# version1.net
KiCad netlist of a schematic drawn in EAGLE
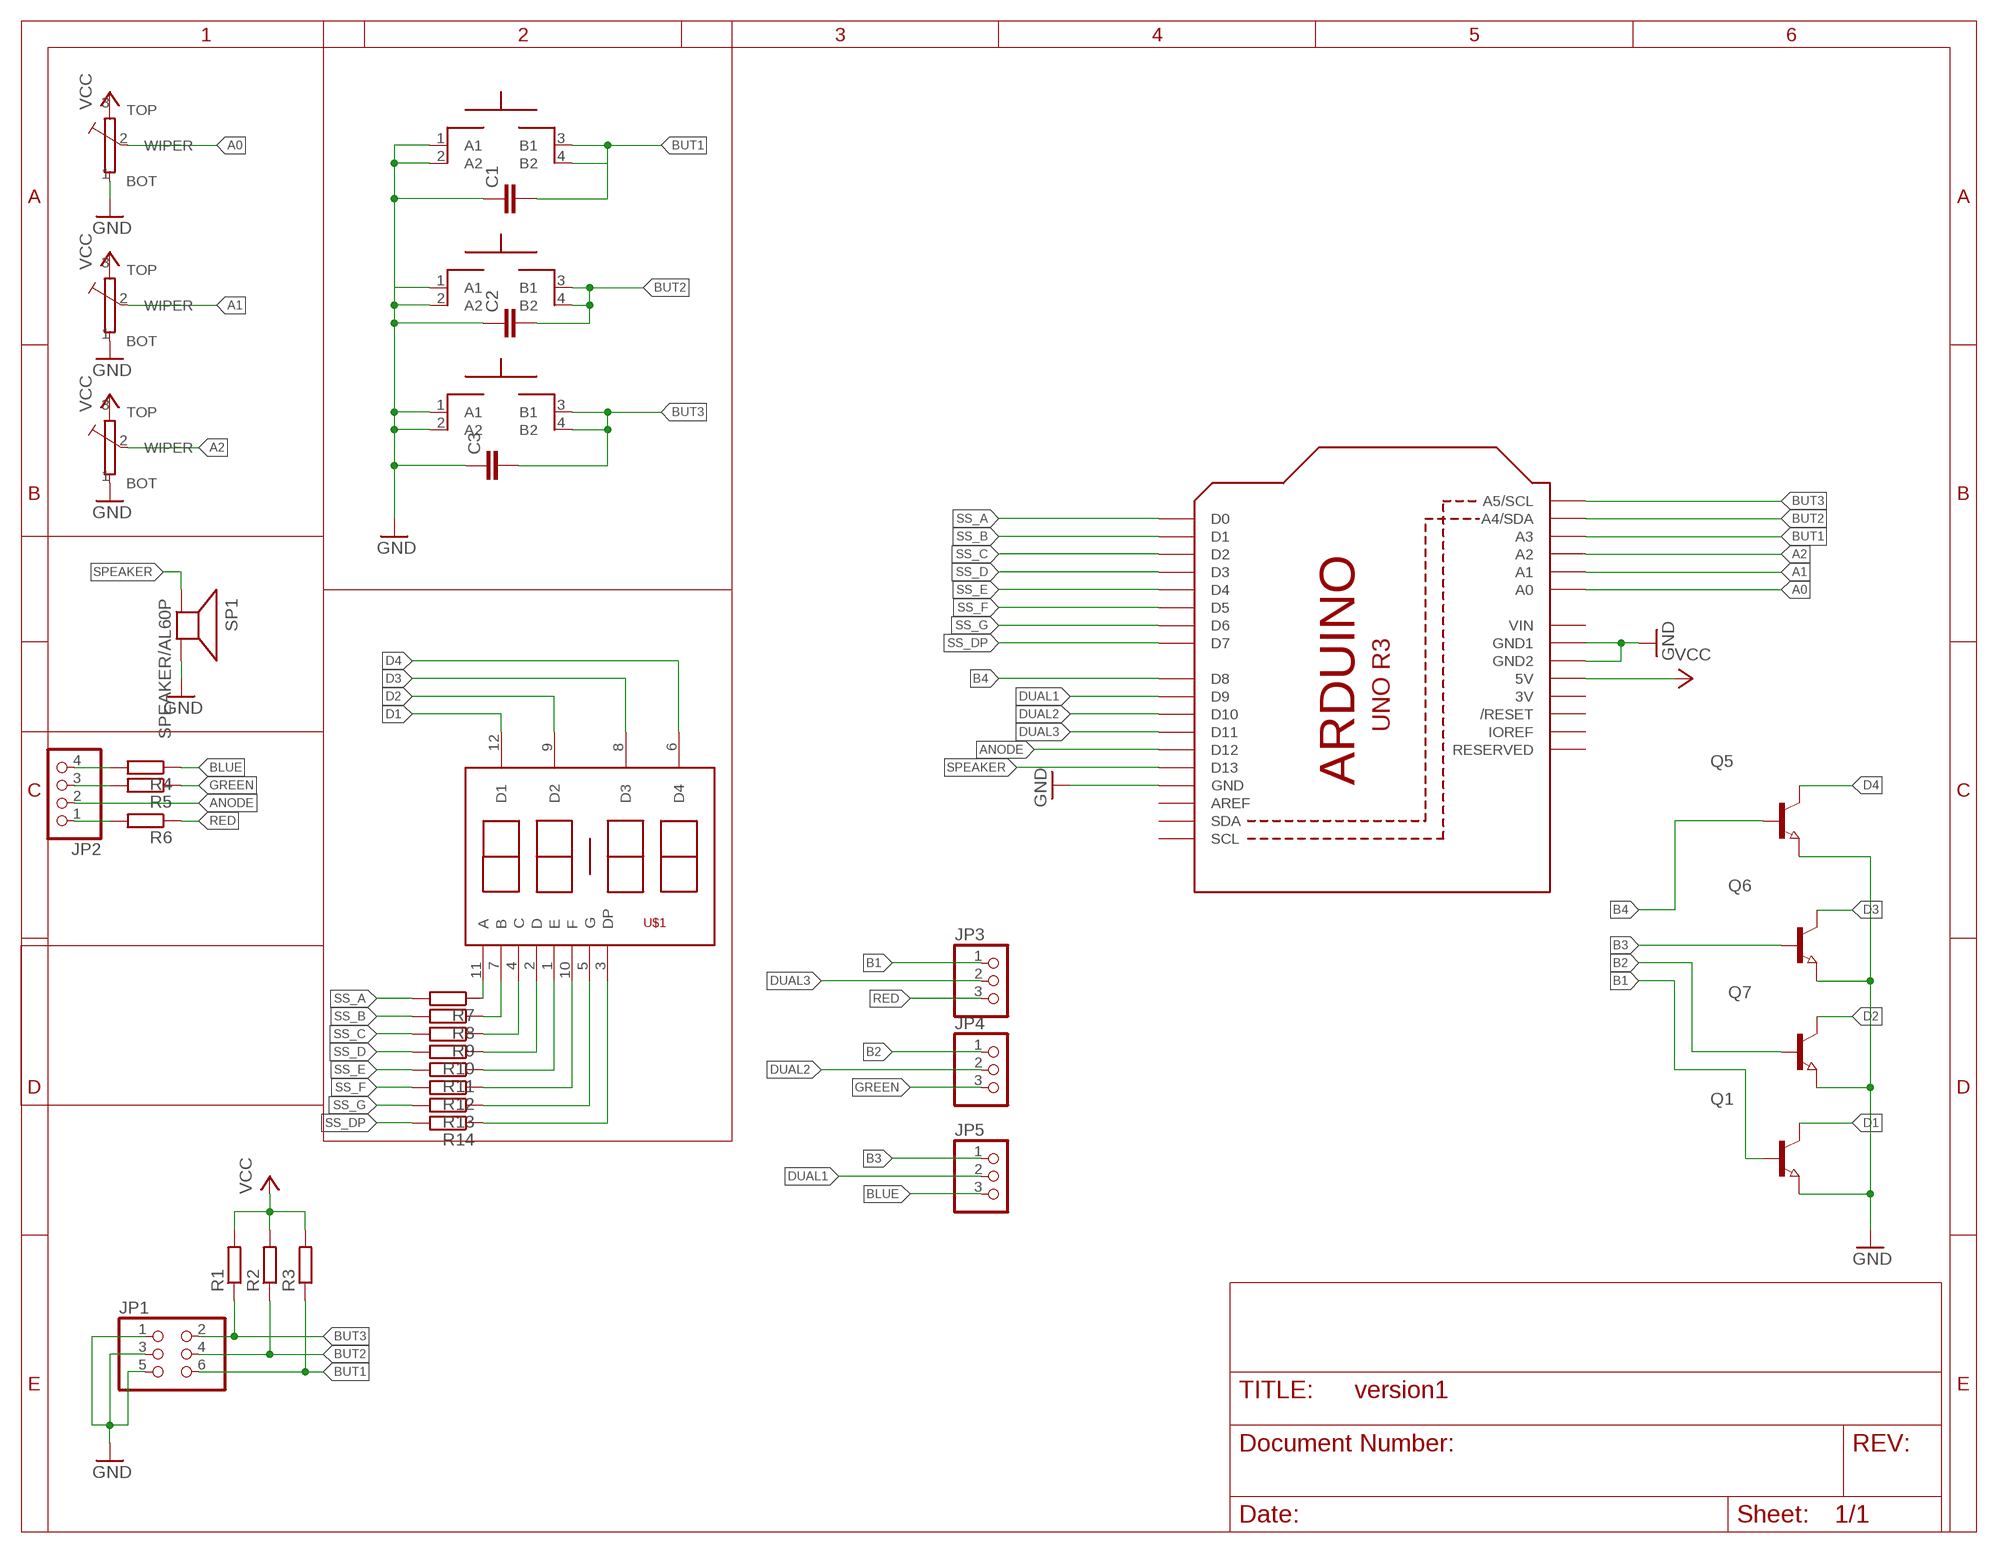
[diagram p0: schematic, sheet 1]

(export (version "E")
  (design (tool "Eeschema 10.0.6"))
  (components
    (comp (ref "C1")
      (value "C-EUC0805")
      (footprint "eagle-import:C0805")
      (libsource (lib "eagle-import") (part "C-EUC0805"))
    )
    (comp (ref "C2")
      (value "C-EUC0805")
      (footprint "eagle-import:C0805")
      (libsource (lib "eagle-import") (part "C-EUC0805"))
    )
    (comp (ref "C3")
      (value "C-EUC0805")
      (footprint "eagle-import:C0805")
      (libsource (lib "eagle-import") (part "C-EUC0805"))
    )
    (comp (ref "JP1")
      (value "PINHD-2X3")
      (footprint "eagle-import:2X03")
      (libsource (lib "eagle-import") (part "PINHD-2X3"))
    )
    (comp (ref "JP2")
      (value "PINHD-1X4")
      (footprint "eagle-import:1X04")
      (libsource (lib "eagle-import") (part "PINHD-1X4"))
    )
    (comp (ref "JP3")
      (value "PINHD-1X3")
      (footprint "eagle-import:1X03")
      (libsource (lib "eagle-import") (part "PINHD-1X3"))
    )
    (comp (ref "JP4")
      (value "PINHD-1X3")
      (footprint "eagle-import:1X03")
      (libsource (lib "eagle-import") (part "PINHD-1X3"))
    )
    (comp (ref "JP5")
      (value "PINHD-1X3")
      (footprint "eagle-import:1X03")
      (libsource (lib "eagle-import") (part "PINHD-1X3"))
    )
    (comp (ref "Q1")
      (value "NPN-TRANSISTOR_SOT23")
      (footprint "eagle-import:SOT23")
      (libsource (lib "eagle-import") (part "NPN-TRANSISTOR_SOT23"))
    )
    (comp (ref "Q5")
      (value "NPN-TRANSISTOR_SOT23")
      (footprint "eagle-import:SOT23")
      (libsource (lib "eagle-import") (part "NPN-TRANSISTOR_SOT23"))
    )
    (comp (ref "Q6")
      (value "NPN-TRANSISTOR_SOT23")
      (footprint "eagle-import:SOT23")
      (libsource (lib "eagle-import") (part "NPN-TRANSISTOR_SOT23"))
    )
    (comp (ref "Q7")
      (value "NPN-TRANSISTOR_SOT23")
      (footprint "eagle-import:SOT23")
      (libsource (lib "eagle-import") (part "NPN-TRANSISTOR_SOT23"))
    )
    (comp (ref "R1")
      (value "R-EU_R0805")
      (footprint "eagle-import:R0805")
      (libsource (lib "eagle-import") (part "R-EU_R0805"))
    )
    (comp (ref "R2")
      (value "R-EU_R0805")
      (footprint "eagle-import:R0805")
      (libsource (lib "eagle-import") (part "R-EU_R0805"))
    )
    (comp (ref "R3")
      (value "R-EU_R0805")
      (footprint "eagle-import:R0805")
      (libsource (lib "eagle-import") (part "R-EU_R0805"))
    )
    (comp (ref "R4")
      (value "R-EU_R0805")
      (footprint "eagle-import:R0805")
      (libsource (lib "eagle-import") (part "R-EU_R0805"))
    )
    (comp (ref "R5")
      (value "R-EU_R0805")
      (footprint "eagle-import:R0805")
      (libsource (lib "eagle-import") (part "R-EU_R0805"))
    )
    (comp (ref "R6")
      (value "R-EU_R0805")
      (footprint "eagle-import:R0805")
      (libsource (lib "eagle-import") (part "R-EU_R0805"))
    )
    (comp (ref "R7")
      (value "R-EU_R0805")
      (footprint "eagle-import:R0805")
      (libsource (lib "eagle-import") (part "R-EU_R0805"))
    )
    (comp (ref "R8")
      (value "R-EU_R0805")
      (footprint "eagle-import:R0805")
      (libsource (lib "eagle-import") (part "R-EU_R0805"))
    )
    (comp (ref "R9")
      (value "R-EU_R0805")
      (footprint "eagle-import:R0805")
      (libsource (lib "eagle-import") (part "R-EU_R0805"))
    )
    (comp (ref "R10")
      (value "R-EU_R0805")
      (footprint "eagle-import:R0805")
      (libsource (lib "eagle-import") (part "R-EU_R0805"))
    )
    (comp (ref "R11")
      (value "R-EU_R0805")
      (footprint "eagle-import:R0805")
      (libsource (lib "eagle-import") (part "R-EU_R0805"))
    )
    (comp (ref "R12")
      (value "R-EU_R0805")
      (footprint "eagle-import:R0805")
      (libsource (lib "eagle-import") (part "R-EU_R0805"))
    )
    (comp (ref "R13")
      (value "R-EU_R0805")
      (footprint "eagle-import:R0805")
      (libsource (lib "eagle-import") (part "R-EU_R0805"))
    )
    (comp (ref "R14")
      (value "R-EU_R0805")
      (footprint "eagle-import:R0805")
      (libsource (lib "eagle-import") (part "R-EU_R0805"))
    )
    (comp (ref "SP1")
      (value "SPEAKER/AL60P")
      (footprint "eagle-import:AL60P")
      (libsource (lib "eagle-import") (part "SPEAKER/AL60P"))
    )
    (comp (ref "SW1")
      (value "MOMENTARYBUTTON")
      (footprint "eagle-import:SPST_NO_SMD")
      (libsource (lib "eagle-import") (part "MOMENTARYBUTTON"))
    )
    (comp (ref "SW2")
      (value "MOMENTARYBUTTON")
      (footprint "eagle-import:SPST_NO_SMD")
      (libsource (lib "eagle-import") (part "MOMENTARYBUTTON"))
    )
    (comp (ref "SW3")
      (value "MOMENTARYBUTTON")
      (footprint "eagle-import:SPST_NO_SMD")
      (libsource (lib "eagle-import") (part "MOMENTARYBUTTON"))
    )
    (comp (ref "TR1")
      (value "TRIMMTHUMB")
      (footprint "eagle-import:RV09")
      (libsource (lib "eagle-import") (part "TRIMMTHUMB"))
    )
    (comp (ref "TR2")
      (value "TRIMMTHUMB")
      (footprint "eagle-import:RV09")
      (libsource (lib "eagle-import") (part "TRIMMTHUMB"))
    )
    (comp (ref "TR3")
      (value "TRIMMTHUMB")
      (footprint "eagle-import:RV09")
      (libsource (lib "eagle-import") (part "TRIMMTHUMB"))
    )
    (comp (ref "U$1")
      (value "4DIG_7SEG_CATHODE")
      (footprint "eagle-import:4DIG_7SEG_CLOCK")
      (libsource (lib "eagle-import") (part "4DIG_7SEG_CATHODE"))
    )
    (comp (ref "U1")
      (value "ARDUINOR3-BPLACE")
      (footprint "eagle-import:ARDUINOR3-BPLACE")
      (libsource (lib "eagle-import") (part "ARDUINOR3-BPLACE"))
    )
  )
  (nets
    (net (code "1") (name "/3V") (class "Default")
      (node (ref "U1") (pin "3V") (pinfunction "3V_3V") (pintype "power_in"))
    )
    (net (code "2") (name "/VIN") (class "Default")
      (node (ref "U1") (pin "VIN") (pinfunction "VIN_VIN") (pintype "power_in"))
    )
    (net (code "3") (name "A0") (class "Default")
      (node (ref "TR1") (pin "2") (pinfunction "WIPER_2") (pintype "bidirectional"))
      (node (ref "U1") (pin "A0") (pinfunction "A0_A0") (pintype "bidirectional"))
    )
    (net (code "4") (name "A1") (class "Default")
      (node (ref "TR2") (pin "2") (pinfunction "WIPER_2") (pintype "bidirectional"))
      (node (ref "U1") (pin "A1") (pinfunction "A1_A1") (pintype "bidirectional"))
    )
    (net (code "5") (name "A2") (class "Default")
      (node (ref "TR3") (pin "2") (pinfunction "WIPER_2") (pintype "bidirectional"))
      (node (ref "U1") (pin "A2") (pinfunction "A2_A2") (pintype "bidirectional"))
    )
    (net (code "6") (name "ANODE") (class "Default")
      (node (ref "JP2") (pin "2") (pinfunction "2_2") (pintype "passive"))
      (node (ref "U1") (pin "D12") (pinfunction "D12_D12") (pintype "bidirectional"))
    )
    (net (code "7") (name "B1") (class "Default")
      (node (ref "JP3") (pin "1") (pinfunction "1_1") (pintype "passive"))
      (node (ref "Q1") (pin "1") (pinfunction "B_1") (pintype "passive"))
    )
    (net (code "8") (name "B2") (class "Default")
      (node (ref "JP4") (pin "1") (pinfunction "1_1") (pintype "passive"))
      (node (ref "Q7") (pin "1") (pinfunction "B_1") (pintype "passive"))
    )
    (net (code "9") (name "B3") (class "Default")
      (node (ref "JP5") (pin "1") (pinfunction "1_1") (pintype "passive"))
      (node (ref "Q6") (pin "1") (pinfunction "B_1") (pintype "passive"))
    )
    (net (code "10") (name "B4") (class "Default")
      (node (ref "Q5") (pin "1") (pinfunction "B_1") (pintype "passive"))
      (node (ref "U1") (pin "D8") (pinfunction "D8_D8") (pintype "bidirectional"))
    )
    (net (code "11") (name "BLUE") (class "Default")
      (node (ref "JP5") (pin "3") (pinfunction "3_3") (pintype "passive"))
      (node (ref "R4") (pin "1") (pinfunction "1_1") (pintype "passive"))
    )
    (net (code "12") (name "BUT1") (class "Default")
      (node (ref "C1") (pin "2") (pinfunction "2_2") (pintype "passive"))
      (node (ref "JP1") (pin "6") (pinfunction "6_6") (pintype "passive"))
      (node (ref "R3") (pin "1") (pinfunction "1_1") (pintype "passive"))
      (node (ref "SW1") (pin "3") (pinfunction "B1_3") (pintype "bidirectional"))
      (node (ref "SW1") (pin "4") (pinfunction "B2_4") (pintype "bidirectional"))
      (node (ref "U1") (pin "A3") (pinfunction "A3_A3") (pintype "bidirectional"))
    )
    (net (code "13") (name "BUT2") (class "Default")
      (node (ref "C2") (pin "2") (pinfunction "2_2") (pintype "passive"))
      (node (ref "JP1") (pin "4") (pinfunction "4_4") (pintype "passive"))
      (node (ref "R2") (pin "1") (pinfunction "1_1") (pintype "passive"))
      (node (ref "SW2") (pin "3") (pinfunction "B1_3") (pintype "bidirectional"))
      (node (ref "SW2") (pin "4") (pinfunction "B2_4") (pintype "bidirectional"))
      (node (ref "U1") (pin "A4") (pinfunction "A4/SDA_A4") (pintype "bidirectional"))
    )
    (net (code "14") (name "BUT3") (class "Default")
      (node (ref "C3") (pin "2") (pinfunction "2_2") (pintype "passive"))
      (node (ref "JP1") (pin "2") (pinfunction "2_2") (pintype "passive"))
      (node (ref "R1") (pin "1") (pinfunction "1_1") (pintype "passive"))
      (node (ref "SW3") (pin "3") (pinfunction "B1_3") (pintype "bidirectional"))
      (node (ref "SW3") (pin "4") (pinfunction "B2_4") (pintype "bidirectional"))
      (node (ref "U1") (pin "A5") (pinfunction "A5/SCL_A5") (pintype "bidirectional"))
    )
    (net (code "15") (name "D1") (class "Default")
      (node (ref "Q1") (pin "3") (pinfunction "C_3") (pintype "passive"))
      (node (ref "U$1") (pin "12") (pinfunction "D1_12") (pintype "bidirectional"))
    )
    (net (code "16") (name "D2") (class "Default")
      (node (ref "Q7") (pin "3") (pinfunction "C_3") (pintype "passive"))
      (node (ref "U$1") (pin "9") (pinfunction "D2_9") (pintype "bidirectional"))
    )
    (net (code "17") (name "D3") (class "Default")
      (node (ref "Q6") (pin "3") (pinfunction "C_3") (pintype "passive"))
      (node (ref "U$1") (pin "8") (pinfunction "D3_8") (pintype "bidirectional"))
    )
    (net (code "18") (name "D4") (class "Default")
      (node (ref "Q5") (pin "3") (pinfunction "C_3") (pintype "passive"))
      (node (ref "U$1") (pin "6") (pinfunction "D4_6") (pintype "bidirectional"))
    )
    (net (code "19") (name "DUAL1") (class "Default")
      (node (ref "JP5") (pin "2") (pinfunction "2_2") (pintype "passive"))
      (node (ref "U1") (pin "D9") (pinfunction "D9_D9") (pintype "bidirectional"))
    )
    (net (code "20") (name "DUAL2") (class "Default")
      (node (ref "JP4") (pin "2") (pinfunction "2_2") (pintype "passive"))
      (node (ref "U1") (pin "D10") (pinfunction "D10_D10") (pintype "bidirectional"))
    )
    (net (code "21") (name "DUAL3") (class "Default")
      (node (ref "JP3") (pin "2") (pinfunction "2_2") (pintype "passive"))
      (node (ref "U1") (pin "D11") (pinfunction "D11_D11") (pintype "bidirectional"))
    )
    (net (code "22") (name "GND") (class "Default")
      (node (ref "C1") (pin "1") (pinfunction "1_1") (pintype "passive"))
      (node (ref "C2") (pin "1") (pinfunction "1_1") (pintype "passive"))
      (node (ref "C3") (pin "1") (pinfunction "1_1") (pintype "passive"))
      (node (ref "JP1") (pin "1") (pinfunction "1_1") (pintype "passive"))
      (node (ref "JP1") (pin "3") (pinfunction "3_3") (pintype "passive"))
      (node (ref "JP1") (pin "5") (pinfunction "5_5") (pintype "passive"))
      (node (ref "Q1") (pin "2") (pinfunction "E_2") (pintype "passive"))
      (node (ref "Q5") (pin "2") (pinfunction "E_2") (pintype "passive"))
      (node (ref "Q6") (pin "2") (pinfunction "E_2") (pintype "passive"))
      (node (ref "Q7") (pin "2") (pinfunction "E_2") (pintype "passive"))
      (node (ref "SP1") (pin "2") (pinfunction "-_2") (pintype "passive"))
      (node (ref "SW1") (pin "1") (pinfunction "A1_1") (pintype "bidirectional"))
      (node (ref "SW1") (pin "2") (pinfunction "A2_2") (pintype "bidirectional"))
      (node (ref "SW2") (pin "1") (pinfunction "A1_1") (pintype "bidirectional"))
      (node (ref "SW2") (pin "2") (pinfunction "A2_2") (pintype "bidirectional"))
      (node (ref "SW3") (pin "1") (pinfunction "A1_1") (pintype "bidirectional"))
      (node (ref "SW3") (pin "2") (pinfunction "A2_2") (pintype "bidirectional"))
      (node (ref "TR1") (pin "1") (pinfunction "BOT_1") (pintype "bidirectional"))
      (node (ref "TR2") (pin "1") (pinfunction "BOT_1") (pintype "bidirectional"))
      (node (ref "TR3") (pin "1") (pinfunction "BOT_1") (pintype "bidirectional"))
      (node (ref "U1") (pin "GND") (pinfunction "GND_GND") (pintype "power_in"))
      (node (ref "U1") (pin "GND1") (pinfunction "GND1_GND1") (pintype "power_in"))
      (node (ref "U1") (pin "GND2") (pinfunction "GND2_GND2") (pintype "power_in"))
    )
    (net (code "23") (name "GREEN") (class "Default")
      (node (ref "JP4") (pin "3") (pinfunction "3_3") (pintype "passive"))
      (node (ref "R5") (pin "1") (pinfunction "1_1") (pintype "passive"))
    )
    (net (code "24") (name "Net-(JP2-Pad1)") (class "Default")
      (node (ref "JP2") (pin "1") (pinfunction "1_1") (pintype "passive"))
      (node (ref "R6") (pin "2") (pinfunction "2_2") (pintype "passive"))
    )
    (net (code "25") (name "Net-(JP2-Pad3)") (class "Default")
      (node (ref "JP2") (pin "3") (pinfunction "3_3") (pintype "passive"))
      (node (ref "R5") (pin "2") (pinfunction "2_2") (pintype "passive"))
    )
    (net (code "26") (name "Net-(JP2-Pad4)") (class "Default")
      (node (ref "JP2") (pin "4") (pinfunction "4_4") (pintype "passive"))
      (node (ref "R4") (pin "2") (pinfunction "2_2") (pintype "passive"))
    )
    (net (code "27") (name "Net-(U$1-A)") (class "Default")
      (node (ref "R7") (pin "1") (pinfunction "1_1") (pintype "passive"))
      (node (ref "U$1") (pin "11") (pinfunction "A_11") (pintype "bidirectional"))
    )
    (net (code "28") (name "Net-(U$1-B)") (class "Default")
      (node (ref "R8") (pin "1") (pinfunction "1_1") (pintype "passive"))
      (node (ref "U$1") (pin "7") (pinfunction "B_7") (pintype "bidirectional"))
    )
    (net (code "29") (name "Net-(U$1-C)") (class "Default")
      (node (ref "R9") (pin "1") (pinfunction "1_1") (pintype "passive"))
      (node (ref "U$1") (pin "4") (pinfunction "C_4") (pintype "bidirectional"))
    )
    (net (code "30") (name "Net-(U$1-D)") (class "Default")
      (node (ref "R10") (pin "1") (pinfunction "1_1") (pintype "passive"))
      (node (ref "U$1") (pin "2") (pinfunction "D_2") (pintype "bidirectional"))
    )
    (net (code "31") (name "Net-(U$1-DP)") (class "Default")
      (node (ref "R14") (pin "1") (pinfunction "1_1") (pintype "passive"))
      (node (ref "U$1") (pin "3") (pinfunction "DP_3") (pintype "bidirectional"))
    )
    (net (code "32") (name "Net-(U$1-E)") (class "Default")
      (node (ref "R11") (pin "1") (pinfunction "1_1") (pintype "passive"))
      (node (ref "U$1") (pin "1") (pinfunction "E_1") (pintype "bidirectional"))
    )
    (net (code "33") (name "Net-(U$1-F)") (class "Default")
      (node (ref "R12") (pin "1") (pinfunction "1_1") (pintype "passive"))
      (node (ref "U$1") (pin "10") (pinfunction "F_10") (pintype "bidirectional"))
    )
    (net (code "34") (name "Net-(U$1-G)") (class "Default")
      (node (ref "R13") (pin "1") (pinfunction "1_1") (pintype "passive"))
      (node (ref "U$1") (pin "5") (pinfunction "G_5") (pintype "bidirectional"))
    )
    (net (code "35") (name "RED") (class "Default")
      (node (ref "JP3") (pin "3") (pinfunction "3_3") (pintype "passive"))
      (node (ref "R6") (pin "1") (pinfunction "1_1") (pintype "passive"))
    )
    (net (code "36") (name "SPEAKER") (class "Default")
      (node (ref "SP1") (pin "1") (pinfunction "+_1") (pintype "passive"))
      (node (ref "U1") (pin "D13") (pinfunction "D13_D13") (pintype "bidirectional"))
    )
    (net (code "37") (name "SS_A") (class "Default")
      (node (ref "R7") (pin "2") (pinfunction "2_2") (pintype "passive"))
      (node (ref "U1") (pin "D0") (pinfunction "D0_D0") (pintype "bidirectional"))
    )
    (net (code "38") (name "SS_B") (class "Default")
      (node (ref "R8") (pin "2") (pinfunction "2_2") (pintype "passive"))
      (node (ref "U1") (pin "D1") (pinfunction "D1_D1") (pintype "bidirectional"))
    )
    (net (code "39") (name "SS_C") (class "Default")
      (node (ref "R9") (pin "2") (pinfunction "2_2") (pintype "passive"))
      (node (ref "U1") (pin "D2") (pinfunction "D2_D2") (pintype "bidirectional"))
    )
    (net (code "40") (name "SS_D") (class "Default")
      (node (ref "R10") (pin "2") (pinfunction "2_2") (pintype "passive"))
      (node (ref "U1") (pin "D3") (pinfunction "D3_D3") (pintype "bidirectional"))
    )
    (net (code "41") (name "SS_DP") (class "Default")
      (node (ref "R14") (pin "2") (pinfunction "2_2") (pintype "passive"))
      (node (ref "U1") (pin "D7") (pinfunction "D7_D7") (pintype "bidirectional"))
    )
    (net (code "42") (name "SS_E") (class "Default")
      (node (ref "R11") (pin "2") (pinfunction "2_2") (pintype "passive"))
      (node (ref "U1") (pin "D4") (pinfunction "D4_D4") (pintype "bidirectional"))
    )
    (net (code "43") (name "SS_F") (class "Default")
      (node (ref "R12") (pin "2") (pinfunction "2_2") (pintype "passive"))
      (node (ref "U1") (pin "D5") (pinfunction "D5_D5") (pintype "bidirectional"))
    )
    (net (code "44") (name "SS_G") (class "Default")
      (node (ref "R13") (pin "2") (pinfunction "2_2") (pintype "passive"))
      (node (ref "U1") (pin "D6") (pinfunction "D6_D6") (pintype "bidirectional"))
    )
    (net (code "45") (name "VCC") (class "Default")
      (node (ref "R1") (pin "2") (pinfunction "2_2") (pintype "passive"))
      (node (ref "R2") (pin "2") (pinfunction "2_2") (pintype "passive"))
      (node (ref "R3") (pin "2") (pinfunction "2_2") (pintype "passive"))
      (node (ref "TR1") (pin "3") (pinfunction "TOP_3") (pintype "bidirectional"))
      (node (ref "TR2") (pin "3") (pinfunction "TOP_3") (pintype "bidirectional"))
      (node (ref "TR3") (pin "3") (pinfunction "TOP_3") (pintype "bidirectional"))
      (node (ref "U1") (pin "5V") (pinfunction "5V_5V") (pintype "power_in"))
    )
    (net (code "46") (name "unconnected-(U1-PadAREF)") (class "Default")
      (node (ref "U1") (pin "AREF") (pinfunction "AREF_AREF") (pintype "bidirectional"))
    )
    (net (code "47") (name "unconnected-(U1-PadIOREF)") (class "Default")
      (node (ref "U1") (pin "IOREF") (pinfunction "IOREF_IOREF") (pintype "output"))
    )
    (net (code "48") (name "unconnected-(U1-PadRESERVED)") (class "Default")
      (node (ref "U1") (pin "RESERVED") (pinfunction "RESERVED_RESERVED") (pintype "no_connect"))
    )
    (net (code "49") (name "unconnected-(U1-PadSCL)") (class "Default")
      (node (ref "U1") (pin "SCL") (pinfunction "SCL_SCL") (pintype "bidirectional"))
    )
    (net (code "50") (name "unconnected-(U1-PadSDA)") (class "Default")
      (node (ref "U1") (pin "SDA") (pinfunction "SDA_SDA") (pintype "bidirectional"))
    )
    (net (code "51") (name "unconnected-(U1-{slash}RESET-PadRESET)") (class "Default")
      (node (ref "U1") (pin "RESET") (pinfunction "/RESET_RESET") (pintype "bidirectional"))
    )
  )
)
